# ld-preamp.net
KiCad netlist of a schematic drawn in EAGLE
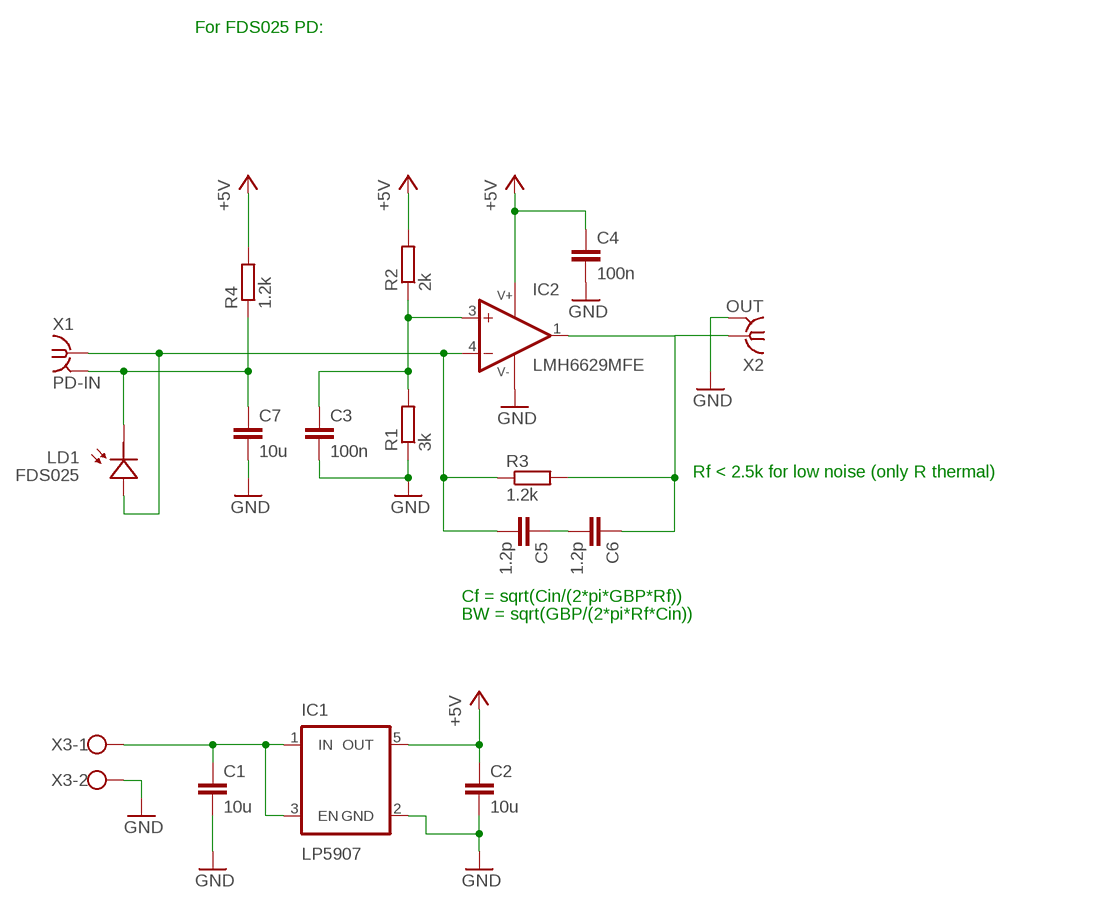
[diagram p0: schematic, sheet 1]

(export (version "E")
  (design (tool "Eeschema 10.0.6"))
  (components
    (comp (ref "C1")
      (value "10u")
      (footprint "eagle-import:C0805")
      (libsource (lib "eagle-import") (part "C-EUC0805"))
    )
    (comp (ref "C2")
      (value "10u")
      (footprint "eagle-import:C0805")
      (libsource (lib "eagle-import") (part "C-EUC0805"))
    )
    (comp (ref "C3")
      (value "100n")
      (footprint "eagle-import:C0603")
      (libsource (lib "eagle-import") (part "C-EUC0603"))
    )
    (comp (ref "C4")
      (value "100n")
      (footprint "eagle-import:C0603")
      (libsource (lib "eagle-import") (part "C-EUC0603"))
    )
    (comp (ref "C5")
      (value "1.2p")
      (footprint "eagle-import:C0603")
      (libsource (lib "eagle-import") (part "C-EUC0603"))
    )
    (comp (ref "C6")
      (value "1.2p")
      (footprint "eagle-import:C0603")
      (libsource (lib "eagle-import") (part "C-EUC0603"))
    )
    (comp (ref "C7")
      (value "10u")
      (footprint "eagle-import:C0805")
      (libsource (lib "eagle-import") (part "C-EUC0805"))
    )
    (comp (ref "IC1")
      (value "LP5907")
      (footprint "eagle-import:SOT23-5")
      (libsource (lib "eagle-import") (part "LP5907"))
    )
    (comp (ref "IC2")
      (value "LMH6629MFE")
      (footprint "eagle-import:SOT23-5")
      (libsource (lib "eagle-import") (part "LMH6629MFE"))
    )
    (comp (ref "LD1")
      (value "FDS025")
      (footprint "eagle-import:PD-TO46-EDGE")
      (libsource (lib "eagle-import") (part "LD-TO46"))
    )
    (comp (ref "R1")
      (value "3k")
      (footprint "eagle-import:R0603")
      (libsource (lib "eagle-import") (part "R-EU_R0603"))
    )
    (comp (ref "R2")
      (value "2k")
      (footprint "eagle-import:R0603")
      (libsource (lib "eagle-import") (part "R-EU_R0603"))
    )
    (comp (ref "R3")
      (value "1.2k")
      (footprint "eagle-import:R0603")
      (libsource (lib "eagle-import") (part "R-EU_R0603"))
    )
    (comp (ref "R4")
      (value "1.2k")
      (footprint "eagle-import:R0603")
      (libsource (lib "eagle-import") (part "R-EU_R0603"))
    )
    (comp (ref "X1")
      (value "PD-IN")
      (footprint "eagle-import:J502-ND-142-0711-821_826")
      (fields (field (name "MF") "JOHNSON COMPONENTS") (field (name "MPN") "142-0711-821"))
      (libsource (lib "eagle-import") (part "SMA-142-0711-821/826"))
    )
    (comp (ref "X2")
      (value "OUT")
      (footprint "eagle-import:J502-ND-142-0711-821_826")
      (fields (field (name "MF") "JOHNSON COMPONENTS") (field (name "MPN") "142-0711-821"))
      (libsource (lib "eagle-import") (part "SMA-142-0711-821/826"))
    )
    (comp (ref "X3")
      (value "W237-102")
      (footprint "eagle-import:W237-102")
      (fields (field (name "MPN") "237-102"))
      (libsource (lib "eagle-import") (part "W237-102"))
    )
  )
  (nets
    (net (code "1") (name "+5V") (class "Default")
      (node (ref "C2") (pin "1") (pinfunction "1_1") (pintype "passive"))
      (node (ref "C4") (pin "1") (pinfunction "1_1") (pintype "passive"))
      (node (ref "IC1") (pin "5") (pinfunction "OUT_5") (pintype "passive"))
      (node (ref "IC2") (pin "5") (pinfunction "V+_5") (pintype "power_in"))
      (node (ref "R2") (pin "2") (pinfunction "2_2") (pintype "passive"))
      (node (ref "R4") (pin "2") (pinfunction "2_2") (pintype "passive"))
    )
    (net (code "2") (name "GND") (class "Default")
      (node (ref "C1") (pin "2") (pinfunction "2_2") (pintype "passive"))
      (node (ref "C2") (pin "2") (pinfunction "2_2") (pintype "passive"))
      (node (ref "C3") (pin "2") (pinfunction "2_2") (pintype "passive"))
      (node (ref "C4") (pin "2") (pinfunction "2_2") (pintype "passive"))
      (node (ref "C7") (pin "2") (pinfunction "2_2") (pintype "passive"))
      (node (ref "IC1") (pin "2") (pinfunction "GND_2") (pintype "input"))
      (node (ref "IC2") (pin "2") (pinfunction "V-_2") (pintype "power_in"))
      (node (ref "R1") (pin "1") (pinfunction "1_1") (pintype "passive"))
      (node (ref "X2") (pin "G@1") (pinfunction "2_G@1") (pintype "passive"))
      (node (ref "X2") (pin "G@2") (pinfunction "2_G@2") (pintype "passive"))
      (node (ref "X2") (pin "G@3") (pinfunction "2_G@3") (pintype "passive"))
      (node (ref "X2") (pin "G@4") (pinfunction "2_G@4") (pintype "passive"))
      (node (ref "X3") (pin "2") (pinfunction "KL_2") (pintype "passive"))
    )
    (net (code "3") (name "Net-(C5-Pad1)") (class "Default")
      (node (ref "C5") (pin "1") (pinfunction "1_1") (pintype "passive"))
      (node (ref "C6") (pin "2") (pinfunction "2_2") (pintype "passive"))
    )
    (net (code "4") (name "Net-(IC1-EN)") (class "Default")
      (node (ref "C1") (pin "1") (pinfunction "1_1") (pintype "passive"))
      (node (ref "IC1") (pin "1") (pinfunction "IN_1") (pintype "input"))
      (node (ref "IC1") (pin "3") (pinfunction "EN_3") (pintype "input"))
      (node (ref "X3") (pin "1") (pinfunction "KL_1") (pintype "passive"))
    )
    (net (code "5") (name "Net-(IC2-+IN)") (class "Default")
      (node (ref "C3") (pin "1") (pinfunction "1_1") (pintype "passive"))
      (node (ref "IC2") (pin "3") (pinfunction "+IN_3") (pintype "input"))
      (node (ref "R1") (pin "2") (pinfunction "2_2") (pintype "passive"))
      (node (ref "R2") (pin "1") (pinfunction "1_1") (pintype "passive"))
    )
    (net (code "6") (name "Net-(IC2--IN)") (class "Default")
      (node (ref "C5") (pin "2") (pinfunction "2_2") (pintype "passive"))
      (node (ref "IC2") (pin "4") (pinfunction "-IN_4") (pintype "input"))
      (node (ref "LD1") (pin "3") (pinfunction "PDA_3") (pintype "passive"))
      (node (ref "R3") (pin "1") (pinfunction "1_1") (pintype "passive"))
      (node (ref "X1") (pin "1") (pinfunction "1_1") (pintype "passive"))
    )
    (net (code "7") (name "Net-(IC2-OUT)") (class "Default")
      (node (ref "C6") (pin "1") (pinfunction "1_1") (pintype "passive"))
      (node (ref "IC2") (pin "1") (pinfunction "OUT_1") (pintype "output"))
      (node (ref "R3") (pin "2") (pinfunction "2_2") (pintype "passive"))
      (node (ref "X2") (pin "1") (pinfunction "1_1") (pintype "passive"))
    )
    (net (code "8") (name "Net-(LD1-PDC)") (class "Default")
      (node (ref "C7") (pin "1") (pinfunction "1_1") (pintype "passive"))
      (node (ref "LD1") (pin "1") (pinfunction "PDC_1") (pintype "passive"))
      (node (ref "R4") (pin "1") (pinfunction "1_1") (pintype "passive"))
      (node (ref "X1") (pin "G@1") (pinfunction "2_G@1") (pintype "passive"))
      (node (ref "X1") (pin "G@2") (pinfunction "2_G@2") (pintype "passive"))
      (node (ref "X1") (pin "G@3") (pinfunction "2_G@3") (pintype "passive"))
      (node (ref "X1") (pin "G@4") (pinfunction "2_G@4") (pintype "passive"))
    )
  )
)
